# PWR_0V9_20A.net
KiCad netlist of a schematic drawn in Altium Designer
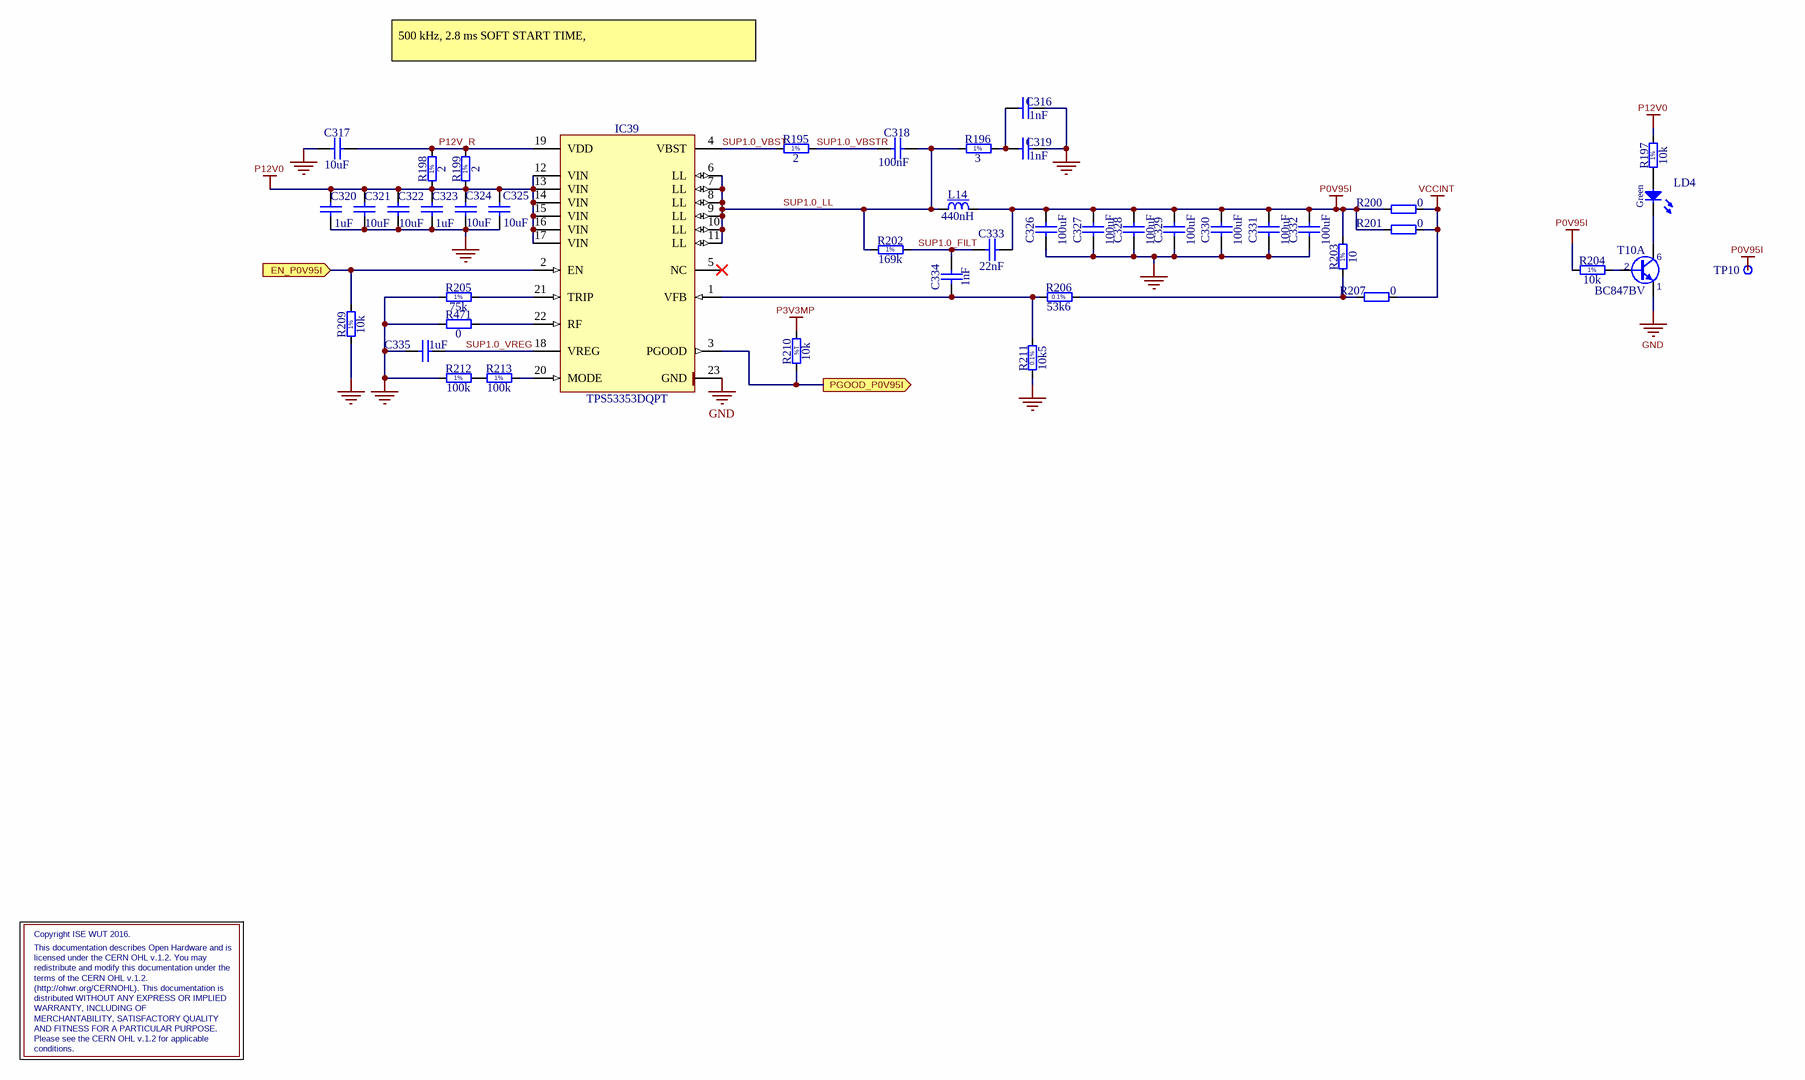
[diagram p0: PWR_0V9_20A.SchDoc]

(export (version "E")
  (design (tool "Eeschema 10.0.6"))
  (components
    (comp (ref "C316")
      (value "1nF")
      (footprint "CAPC1005X55N")
      (description "Non-polarised capacitor")
      (fields
        (field (name "MANUFACTURER PART NUMBER") "CC0402_1NF_50V_10%_X7R")
        (field (name "MANUFACTURER") "GENERIC")
        (field (name "AUTHOR") "CERN DEM JLC")
      )
      (libsource (lib "Capacitors") (part "Capacitor - non polarized"))
    )
    (comp (ref "C317")
      (value "10uF")
      (footprint "CAPC3216X180N")
      (description "Non-polarised capacitor")
      (fields
        (field (name "MANUFACTURER PART NUMBER") "CC1206_10uF_25V_10%_X7R")
        (field (name "MANUFACTURER") "GENERIC")
        (field (name "AUTHOR") "CERN DEM JLC")
      )
      (libsource (lib "Capacitors") (part "Capacitor - non polarized"))
    )
    (comp (ref "C318")
      (value "100nF")
      (footprint "CAPC1005X55N")
      (description "Non-polarised capacitor")
      (fields
        (field (name "MANUFACTURER PART NUMBER") "CC0402_100NF_16V_10%_X5R")
        (field (name "MANUFACTURER") "GENERIC")
        (field (name "AUTHOR") "CERN DEM JLC")
      )
      (libsource (lib "Capacitors") (part "Capacitor - non polarized"))
    )
    (comp (ref "C319")
      (value "1nF")
      (footprint "CAPC1005X55N")
      (description "Non-polarised capacitor")
      (fields
        (field (name "MANUFACTURER PART NUMBER") "CC0402_1NF_50V_10%_X7R")
        (field (name "MANUFACTURER") "GENERIC")
        (field (name "AUTHOR") "CERN DEM JLC")
      )
      (libsource (lib "Capacitors") (part "Capacitor - non polarized"))
    )
    (comp (ref "C320")
      (value "1uF")
      (footprint "CAPC1608X87N")
      (description "Non-polarised capacitor")
      (fields
        (field (name "MANUFACTURER PART NUMBER") "CC0603_1UF_25V_10%_X7R")
        (field (name "MANUFACTURER") "GENERIC")
        (field (name "AUTHOR") "CERN DEM JLC")
      )
      (libsource (lib "Capacitors") (part "Capacitor - non polarized"))
    )
    (comp (ref "C321")
      (value "10uF")
      (footprint "CAPC3216X180N")
      (description "Non-polarised capacitor")
      (fields
        (field (name "MANUFACTURER PART NUMBER") "CC1206_10uF_25V_10%_X7R")
        (field (name "MANUFACTURER") "GENERIC")
        (field (name "AUTHOR") "CERN DEM JLC")
      )
      (libsource (lib "Capacitors") (part "Capacitor - non polarized"))
    )
    (comp (ref "C322")
      (value "10uF")
      (footprint "CAPC3216X180N")
      (description "Non-polarised capacitor")
      (fields
        (field (name "MANUFACTURER PART NUMBER") "CC1206_10uF_25V_10%_X7R")
        (field (name "MANUFACTURER") "GENERIC")
        (field (name "AUTHOR") "CERN DEM JLC")
      )
      (libsource (lib "Capacitors") (part "Capacitor - non polarized"))
    )
    (comp (ref "C323")
      (value "1uF")
      (footprint "CAPC1608X87N")
      (description "Non-polarised capacitor")
      (fields
        (field (name "MANUFACTURER PART NUMBER") "CC0603_1UF_25V_10%_X7R")
        (field (name "MANUFACTURER") "GENERIC")
        (field (name "AUTHOR") "CERN DEM JLC")
      )
      (libsource (lib "Capacitors") (part "Capacitor - non polarized"))
    )
    (comp (ref "C324")
      (value "10uF")
      (footprint "CAPC3216X180N")
      (description "Non-polarised capacitor")
      (fields
        (field (name "MANUFACTURER PART NUMBER") "CC1206_10uF_25V_10%_X7R")
        (field (name "MANUFACTURER") "GENERIC")
        (field (name "AUTHOR") "CERN DEM JLC")
      )
      (libsource (lib "Capacitors") (part "Capacitor - non polarized"))
    )
    (comp (ref "C325")
      (value "10uF")
      (footprint "CAPC3216X180N")
      (description "Non-polarised capacitor")
      (fields
        (field (name "MANUFACTURER PART NUMBER") "CC1206_10uF_25V_10%_X7R")
        (field (name "MANUFACTURER") "GENERIC")
        (field (name "AUTHOR") "CERN DEM JLC")
      )
      (libsource (lib "Capacitors") (part "Capacitor - non polarized"))
    )
    (comp (ref "C326")
      (value "100uF")
      (footprint "CAPC3216X180N")
      (description "Non-polarised capacitor")
      (fields
        (field (name "MANUFACTURER PART NUMBER") "CC1206_100UF_6.3V_20%_X5R")
        (field (name "MANUFACTURER") "GENERIC")
        (field (name "AUTHOR") "CERN DEM JLC")
      )
      (libsource (lib "Capacitors") (part "Capacitor - non polarized"))
    )
    (comp (ref "C327")
      (value "100uF")
      (footprint "CAPC3216X180N")
      (description "Non-polarised capacitor")
      (fields
        (field (name "MANUFACTURER PART NUMBER") "CC1206_100UF_6.3V_20%_X5R")
        (field (name "MANUFACTURER") "GENERIC")
        (field (name "AUTHOR") "CERN DEM JLC")
      )
      (libsource (lib "Capacitors") (part "Capacitor - non polarized"))
    )
    (comp (ref "C328")
      (value "100uF")
      (footprint "CAPC3216X180N")
      (description "Non-polarised capacitor")
      (fields
        (field (name "MANUFACTURER PART NUMBER") "CC1206_100UF_6.3V_20%_X5R")
        (field (name "MANUFACTURER") "GENERIC")
        (field (name "AUTHOR") "CERN DEM JLC")
      )
      (libsource (lib "Capacitors") (part "Capacitor - non polarized"))
    )
    (comp (ref "C329")
      (value "100uF")
      (footprint "CAPC3216X180N")
      (description "Non-polarised capacitor")
      (fields
        (field (name "MANUFACTURER PART NUMBER") "CC1206_100UF_6.3V_20%_X5R")
        (field (name "MANUFACTURER") "GENERIC")
        (field (name "AUTHOR") "CERN DEM JLC")
      )
      (libsource (lib "Capacitors") (part "Capacitor - non polarized"))
    )
    (comp (ref "C330")
      (value "100uF")
      (footprint "CAPC3216X180N")
      (description "Non-polarised capacitor")
      (fields
        (field (name "MANUFACTURER PART NUMBER") "CC1206_100UF_6.3V_20%_X5R")
        (field (name "MANUFACTURER") "GENERIC")
        (field (name "AUTHOR") "CERN DEM JLC")
      )
      (libsource (lib "Capacitors") (part "Capacitor - non polarized"))
    )
    (comp (ref "C331")
      (value "100uF")
      (footprint "CAPC3216X180N")
      (description "Non-polarised capacitor")
      (fields
        (field (name "MANUFACTURER PART NUMBER") "CC1206_100UF_6.3V_20%_X5R")
        (field (name "MANUFACTURER") "GENERIC")
        (field (name "AUTHOR") "CERN DEM JLC")
      )
      (libsource (lib "Capacitors") (part "Capacitor - non polarized"))
    )
    (comp (ref "C332")
      (value "100uF")
      (footprint "CAPC3216X180N")
      (description "Non-polarised capacitor")
      (fields
        (field (name "MANUFACTURER PART NUMBER") "CC1206_100UF_6.3V_20%_X5R")
        (field (name "MANUFACTURER") "GENERIC")
        (field (name "AUTHOR") "CERN DEM JLC")
      )
      (libsource (lib "Capacitors") (part "Capacitor - non polarized"))
    )
    (comp (ref "C333")
      (value "22nF")
      (footprint "CAPC1608X87N")
      (description "Non-polarised capacitor")
      (fields
        (field (name "MANUFACTURER PART NUMBER") "CC0603_22NF_50V_10%_X7R")
        (field (name "MANUFACTURER") "GENERIC")
        (field (name "AUTHOR") "CERN DEM JLC")
      )
      (libsource (lib "Capacitors") (part "Capacitor - non polarized"))
    )
    (comp (ref "C334")
      (value "1nF")
      (footprint "CAPC1005X55N")
      (description "Non-polarised capacitor")
      (fields
        (field (name "MANUFACTURER PART NUMBER") "CC0402_1NF_50V_10%_X7R")
        (field (name "MANUFACTURER") "GENERIC")
        (field (name "AUTHOR") "CERN DEM JLC")
      )
      (libsource (lib "Capacitors") (part "Capacitor - non polarized"))
    )
    (comp (ref "C335")
      (value "1uF")
      (footprint "CAPC1608X87N")
      (description "Non-polarised capacitor")
      (fields
        (field (name "MANUFACTURER PART NUMBER") "CC0603_1UF_25V_10%_X7R")
        (field (name "MANUFACTURER") "GENERIC")
        (field (name "AUTHOR") "CERN DEM JLC")
      )
      (libsource (lib "Capacitors") (part "Capacitor - non polarized"))
    )
    (comp (ref "IC39")
      (value "TPS53353DQPT")
      (footprint "SON50P500X600X150-23N-R334X557")
      (description "1.5V to 15V Input (4.5V to 25V Bias), 20A Synchronous Buck SWIFT™ Converter with Eco-mode™")
      (fields (field (name "MANUFACTURER") "TEXAS INSTRUMENTS"))
      (libsource (lib "TP_LIB") (part "TPS53353DQPT"))
    )
    (comp (ref "L14")
      (value "440nH")
      (footprint "IND_PULSE_PA0513")
      (description "Inductor With Core")
      (fields
        (field (name "MANUFACTURER PART NUMBER") "PA0513.441NLT")
        (field (name "MANUFACTURER") "PULSE ELECTRONICS")
        (field (name "AUTHOR") "CERN DEM JLC")
      )
      (libsource (lib "Inductors & Transformers") (part "Inductor With Magnetic core"))
    )
    (comp (ref "LD4")
      (value "Green")
      (footprint "LED_OSRAM_LGL29K")
      (description "LED Green 1C 2A")
      (fields
        (field (name "MANUFACTURER PART NUMBER") "LG L29K-G2J1-24-Z")
        (field (name "MANUFACTURER") "OSRAM")
        (field (name "AUTHOR") "CERN DEM JLC")
      )
      (libsource (lib "ICs And Semiconductors") (part "LED Green 1C 2A"))
    )
    (comp (ref "R195")
      (value "2")
      (footprint "RESC1608X55N")
      (description "Resistor - 1%")
      (fields
        (field (name "MANUFACTURER PART NUMBER") "R0603_2R_1%_0.1W_200PPM")
        (field (name "MANUFACTURER") "GENERIC")
        (field (name "AUTHOR") "CERN DEM JLC")
      )
      (libsource (lib "Resistors") (part "Resistor - 1%"))
    )
    (comp (ref "R196")
      (value "3")
      (footprint "RESC3216X65N")
      (description "Resistor - 1%")
      (fields
        (field (name "MANUFACTURER PART NUMBER") "R1206_3R_1%_0.25W_200PPM")
        (field (name "MANUFACTURER") "GENERIC")
        (field (name "AUTHOR") "CERN DEM JLC")
      )
      (libsource (lib "Resistors") (part "Resistor - 1%"))
    )
    (comp (ref "R197")
      (value "10k")
      (footprint "RESC1005X40N")
      (description "Resistor - 1%")
      (fields
        (field (name "PART NUMBER") "R0402_10K_1%_0.0625W_100PPM")
        (field (name "POWER") "0.0625W")
        (field (name "AUTHOR") "CERN DEM JLC")
      )
      (libsource (lib "Resistors") (part "Resistor - 1%"))
    )
    (comp (ref "R198")
      (value "2")
      (footprint "RESC1608X55N")
      (description "Resistor - 1%")
      (fields
        (field (name "MANUFACTURER PART NUMBER") "R0603_2R_1%_0.1W_200PPM")
        (field (name "MANUFACTURER") "GENERIC")
        (field (name "AUTHOR") "CERN DEM JLC")
      )
      (libsource (lib "Resistors") (part "Resistor - 1%"))
    )
    (comp (ref "R199")
      (value "2")
      (footprint "RESC1608X55N")
      (description "Resistor - 1%")
      (fields
        (field (name "MANUFACTURER PART NUMBER") "R0603_2R_1%_0.1W_200PPM")
        (field (name "MANUFACTURER") "GENERIC")
        (field (name "AUTHOR") "CERN DEM JLC")
      )
      (libsource (lib "Resistors") (part "Resistor - 1%"))
    )
    (comp (ref "R200")
      (value "0")
      (footprint "RESC6331X70N")
      (description "Resistor")
      (fields
        (field (name "MANUFACTURER PART NUMBER") "R2512_0R_JUMPER")
        (field (name "MANUFACTURER") "GENERIC")
        (field (name "AUTHOR") "CERN DEM JLC")
      )
      (libsource (lib "Resistors") (part "Resistor"))
    )
    (comp (ref "R201")
      (value "0")
      (footprint "RESC6331X70N")
      (description "Resistor")
      (fields
        (field (name "MANUFACTURER PART NUMBER") "R2512_0R_JUMPER")
        (field (name "MANUFACTURER") "GENERIC")
        (field (name "AUTHOR") "CERN DEM JLC")
      )
      (libsource (lib "Resistors") (part "Resistor"))
    )
    (comp (ref "R202")
      (value "169k")
      (footprint "RESC1608X55N")
      (description "Resistor - 1%")
      (fields
        (field (name "MANUFACTURER PART NUMBER") "R0603_169K_1%_0.1W_100PPM")
        (field (name "MANUFACTURER") "GENERIC")
        (field (name "AUTHOR") "CERN DEM JLC")
      )
      (libsource (lib "Resistors") (part "Resistor - 1%"))
    )
    (comp (ref "R203")
      (value "10")
      (footprint "RESC1005X40N")
      (description "Resistor - 1%")
      (fields
        (field (name "MANUFACTURER PART NUMBER") "R0402_10R_1%_0.0625W_200PPM")
        (field (name "MANUFACTURER") "GENERIC")
        (field (name "AUTHOR") "CERN DEM JLC")
      )
      (libsource (lib "Resistors") (part "Resistor - 1%"))
    )
    (comp (ref "R204")
      (value "10k")
      (footprint "RESC1005X40N")
      (description "Resistor - 1%")
      (fields
        (field (name "MANUFACTURER PART NUMBER") "R0402_10K_1%_0.0625W_100PPM")
        (field (name "MANUFACTURER") "GENERIC")
        (field (name "AUTHOR") "CERN DEM JLC")
      )
      (libsource (lib "Resistors") (part "Resistor - 1%"))
    )
    (comp (ref "R205")
      (value "75k")
      (footprint "RESC1005X40N")
      (description "Resistor - 1%")
      (fields
        (field (name "MANUFACTURER PART NUMBER") "R0402_75K_1%_0.0625W_100PPM")
        (field (name "MANUFACTURER") "GENERIC")
        (field (name "AUTHOR") "CERN DEM JLC")
      )
      (libsource (lib "Resistors") (part "Resistor - 1%"))
    )
    (comp (ref "R206")
      (value "53k6")
      (footprint "RESC1608X55N")
      (description "Resistor - 0.1%")
      (fields
        (field (name "PART NUMBER") "R0603_53K6_0.1%_0.063W_10PPM")
        (field (name "POWER") "0.063W")
        (field (name "AUTHOR") "CERN DEM JLC")
      )
      (libsource (lib "Resistors") (part "Resistor - 0.1%"))
    )
    (comp (ref "R207")
      (value "0")
      (footprint "RESC6331X70N")
      (description "Resistor")
      (fields
        (field (name "MANUFACTURER PART NUMBER") "R2512_0R_JUMPER")
        (field (name "MANUFACTURER") "GENERIC")
        (field (name "AUTHOR") "CERN DEM JLC")
      )
      (libsource (lib "Resistors") (part "Resistor"))
    )
    (comp (ref "R209")
      (value "10k")
      (footprint "RESC1005X40N")
      (description "Resistor - 1%")
      (fields
        (field (name "MANUFACTURER PART NUMBER") "R0402_10K_1%_0.0625W_100PPM")
        (field (name "MANUFACTURER") "GENERIC")
        (field (name "AUTHOR") "CERN DEM JLC")
      )
      (libsource (lib "Resistors") (part "Resistor - 1%"))
    )
    (comp (ref "R210")
      (value "10k")
      (footprint "RESC1005X40N")
      (description "Resistor - 1%")
      (fields
        (field (name "MANUFACTURER PART NUMBER") "R0402_10K_1%_0.0625W_100PPM")
        (field (name "MANUFACTURER") "GENERIC")
        (field (name "AUTHOR") "CERN DEM JLC")
      )
      (libsource (lib "Resistors") (part "Resistor - 1%"))
    )
    (comp (ref "R211")
      (value "10k5")
      (footprint "RESC1608X55N")
      (description "Resistor - 0.1%")
      (fields
        (field (name "PART NUMBER") "R0603_10K5_0.1%_0.063W_10PPM")
        (field (name "POWER") "0.063W")
        (field (name "AUTHOR") "CERN DEM JLC")
      )
      (libsource (lib "Resistors") (part "Resistor - 0.1%"))
    )
    (comp (ref "R212")
      (value "100k")
      (footprint "RESC1005X40N")
      (description "Resistor - 1%")
      (fields
        (field (name "MANUFACTURER PART NUMBER") "R0402_100K_1%_0.0625W_100PPM")
        (field (name "MANUFACTURER") "GENERIC")
        (field (name "AUTHOR") "CERN DEM JLC")
      )
      (libsource (lib "Resistors") (part "Resistor - 1%"))
    )
    (comp (ref "R213")
      (value "100k")
      (footprint "RESC1005X40N")
      (description "Resistor - 1%")
      (fields
        (field (name "MANUFACTURER PART NUMBER") "R0402_100K_1%_0.0625W_100PPM")
        (field (name "MANUFACTURER") "GENERIC")
        (field (name "AUTHOR") "CERN DEM JLC")
      )
      (libsource (lib "Resistors") (part "Resistor - 1%"))
    )
    (comp (ref "R471")
      (value "0")
      (footprint "RESC1005X40N")
      (description "Resistor")
      (fields
        (field (name "PART NUMBER") "R0402_0R_JUMPER")
        (field (name "MANUFACTURER") "GENERIC")
        (field (name "AUTHOR") "CERN DEM JLC")
      )
      (libsource (lib "Resistors") (part "Resistor"))
    )
    (comp (ref "T10")
      (value "BC847BV")
      (footprint "SOTFL50P160X60-6N")
      (description "45V, 100mA NPN General Purpose Double Transistor")
      (fields (field (name "MANUFACTURER") "NXP SEMICONDUCTORS") (field (name "AUTHOR") "CERN DEM JLC"))
      (libsource (lib "ICs And Semiconductors") (part "BC847BV"))
    )
    (comp (ref "TP10")
      (value "Test Point")
      (footprint "TPS127")
      (fields (field (name "PART NUMBER") "SMD_PAD_1.27X1.27MM") (field (name "AUTHOR") "CERN DEM JLC"))
      (libsource (lib "Eletro-mechanical") (part "Test Point"))
    )
  )
  (nets
    (net (code "1") (name "/EN_P0V95I") (class "Default")
      (node (ref "IC39") (pin "2") (pinfunction "EN_2") (pintype "input"))
      (node (ref "R209") (pin "1") (pinfunction "1_1") (pintype "passive"))
    )
    (net (code "2") (name "/P12V_R") (class "Default")
      (node (ref "C317") (pin "1") (pinfunction "1_1") (pintype "passive"))
      (node (ref "IC39") (pin "19") (pinfunction "VDD_19") (pintype "power_in"))
      (node (ref "R198") (pin "2") (pinfunction "2_2") (pintype "passive"))
      (node (ref "R199") (pin "2") (pinfunction "2_2") (pintype "passive"))
    )
    (net (code "3") (name "/PGOOD_P0V95I") (class "Default")
      (node (ref "IC39") (pin "3") (pinfunction "PGOOD_3") (pintype "output"))
      (node (ref "R210") (pin "1") (pinfunction "1_1") (pintype "passive"))
    )
    (net (code "4") (name "/SUP1.0_FILT") (class "Default")
      (node (ref "C333") (pin "1") (pinfunction "1_1") (pintype "passive"))
      (node (ref "C334") (pin "2") (pinfunction "2_2") (pintype "passive"))
      (node (ref "R202") (pin "2") (pinfunction "2_2") (pintype "passive"))
    )
    (net (code "5") (name "/SUP1.0_LL") (class "Default")
      (node (ref "C318") (pin "2") (pinfunction "2_2") (pintype "passive"))
      (node (ref "IC39") (pin "10") (pinfunction "LL_10") (pintype "bidirectional"))
      (node (ref "IC39") (pin "11") (pinfunction "LL_11") (pintype "bidirectional"))
      (node (ref "IC39") (pin "6") (pinfunction "LL_6") (pintype "bidirectional"))
      (node (ref "IC39") (pin "7") (pinfunction "LL_7") (pintype "bidirectional"))
      (node (ref "IC39") (pin "8") (pinfunction "LL_8") (pintype "bidirectional"))
      (node (ref "IC39") (pin "9") (pinfunction "LL_9") (pintype "bidirectional"))
      (node (ref "L14") (pin "1") (pinfunction "1_1") (pintype "passive"))
      (node (ref "R196") (pin "1") (pinfunction "1_1") (pintype "passive"))
      (node (ref "R202") (pin "1") (pinfunction "1_1") (pintype "passive"))
    )
    (net (code "6") (name "/SUP1.0_VBST") (class "Default")
      (node (ref "IC39") (pin "4") (pinfunction "VBST_4") (pintype "power_in"))
      (node (ref "R195") (pin "1") (pinfunction "1_1") (pintype "passive"))
    )
    (net (code "7") (name "/SUP1.0_VBSTR") (class "Default")
      (node (ref "C318") (pin "1") (pinfunction "1_1") (pintype "passive"))
      (node (ref "R195") (pin "2") (pinfunction "2_2") (pintype "passive"))
    )
    (net (code "8") (name "/SUP1.0_VREG") (class "Default")
      (node (ref "C335") (pin "1") (pinfunction "1_1") (pintype "passive"))
      (node (ref "IC39") (pin "18") (pinfunction "VREG_18") (pintype "power_in"))
    )
    (net (code "9") (name "GND") (class "Default")
      (node (ref "C316") (pin "2") (pinfunction "2_2") (pintype "passive"))
      (node (ref "C317") (pin "2") (pinfunction "2_2") (pintype "passive"))
      (node (ref "C319") (pin "2") (pinfunction "2_2") (pintype "passive"))
      (node (ref "C320") (pin "1") (pinfunction "1_1") (pintype "passive"))
      (node (ref "C321") (pin "1") (pinfunction "1_1") (pintype "passive"))
      (node (ref "C322") (pin "1") (pinfunction "1_1") (pintype "passive"))
      (node (ref "C323") (pin "1") (pinfunction "1_1") (pintype "passive"))
      (node (ref "C324") (pin "1") (pinfunction "1_1") (pintype "passive"))
      (node (ref "C325") (pin "1") (pinfunction "1_1") (pintype "passive"))
      (node (ref "C326") (pin "1") (pinfunction "1_1") (pintype "passive"))
      (node (ref "C327") (pin "1") (pinfunction "1_1") (pintype "passive"))
      (node (ref "C328") (pin "1") (pinfunction "1_1") (pintype "passive"))
      (node (ref "C329") (pin "1") (pinfunction "1_1") (pintype "passive"))
      (node (ref "C330") (pin "1") (pinfunction "1_1") (pintype "passive"))
      (node (ref "C331") (pin "1") (pinfunction "1_1") (pintype "passive"))
      (node (ref "C332") (pin "1") (pinfunction "1_1") (pintype "passive"))
      (node (ref "C335") (pin "2") (pinfunction "2_2") (pintype "passive"))
      (node (ref "IC39") (pin "23") (pinfunction "GND_23") (pintype "power_in"))
      (node (ref "R205") (pin "1") (pinfunction "1_1") (pintype "passive"))
      (node (ref "R209") (pin "2") (pinfunction "2_2") (pintype "passive"))
      (node (ref "R211") (pin "1") (pinfunction "1_1") (pintype "passive"))
      (node (ref "R212") (pin "1") (pinfunction "1_1") (pintype "passive"))
      (node (ref "R471") (pin "1") (pinfunction "1_1") (pintype "passive"))
      (node (ref "T10") (pin "1") (pinfunction "E_1") (pintype "passive"))
    )
    (net (code "10") (name "Net-(C316-Pad1)") (class "Default")
      (node (ref "C316") (pin "1") (pinfunction "1_1") (pintype "passive"))
      (node (ref "C319") (pin "1") (pinfunction "1_1") (pintype "passive"))
      (node (ref "R196") (pin "2") (pinfunction "2_2") (pintype "passive"))
    )
    (net (code "11") (name "Net-(IC39-MODE)") (class "Default")
      (node (ref "IC39") (pin "20") (pinfunction "MODE_20") (pintype "input"))
      (node (ref "R213") (pin "2") (pinfunction "2_2") (pintype "passive"))
    )
    (net (code "12") (name "Net-(IC39-RF)") (class "Default")
      (node (ref "IC39") (pin "22") (pinfunction "RF_22") (pintype "input"))
      (node (ref "R471") (pin "2") (pinfunction "2_2") (pintype "passive"))
    )
    (net (code "13") (name "Net-(IC39-TRIP)") (class "Default")
      (node (ref "IC39") (pin "21") (pinfunction "TRIP_21") (pintype "input"))
      (node (ref "R205") (pin "2") (pinfunction "2_2") (pintype "passive"))
    )
    (net (code "14") (name "Net-(IC39-VFB)") (class "Default")
      (node (ref "C334") (pin "1") (pinfunction "1_1") (pintype "passive"))
      (node (ref "IC39") (pin "1") (pinfunction "VFB_1") (pintype "input"))
      (node (ref "R206") (pin "1") (pinfunction "1_1") (pintype "passive"))
      (node (ref "R211") (pin "2") (pinfunction "2_2") (pintype "passive"))
    )
    (net (code "15") (name "Net-(LD4-A)") (class "Default")
      (node (ref "LD4") (pin "2") (pinfunction "A_2") (pintype "passive"))
      (node (ref "R197") (pin "1") (pinfunction "1_1") (pintype "passive"))
    )
    (net (code "16") (name "Net-(LD4-C)") (class "Default")
      (node (ref "LD4") (pin "1") (pinfunction "C_1") (pintype "passive"))
      (node (ref "T10") (pin "6") (pinfunction "C_6") (pintype "passive"))
    )
    (net (code "17") (name "Net-(R203-Pad1)") (class "Default")
      (node (ref "R203") (pin "1") (pinfunction "1_1") (pintype "passive"))
      (node (ref "R206") (pin "2") (pinfunction "2_2") (pintype "passive"))
      (node (ref "R207") (pin "1") (pinfunction "1_1") (pintype "passive"))
    )
    (net (code "18") (name "Net-(R212-Pad2)") (class "Default")
      (node (ref "R212") (pin "2") (pinfunction "2_2") (pintype "passive"))
      (node (ref "R213") (pin "1") (pinfunction "1_1") (pintype "passive"))
    )
    (net (code "19") (name "Net-(T10A-B)") (class "Default")
      (node (ref "R204") (pin "2") (pinfunction "2_2") (pintype "passive"))
      (node (ref "T10") (pin "2") (pinfunction "B_2") (pintype "passive"))
    )
    (net (code "20") (name "P0V95I") (class "Default")
      (node (ref "C326") (pin "2") (pinfunction "2_2") (pintype "passive"))
      (node (ref "C327") (pin "2") (pinfunction "2_2") (pintype "passive"))
      (node (ref "C328") (pin "2") (pinfunction "2_2") (pintype "passive"))
      (node (ref "C329") (pin "2") (pinfunction "2_2") (pintype "passive"))
      (node (ref "C330") (pin "2") (pinfunction "2_2") (pintype "passive"))
      (node (ref "C331") (pin "2") (pinfunction "2_2") (pintype "passive"))
      (node (ref "C332") (pin "2") (pinfunction "2_2") (pintype "passive"))
      (node (ref "C333") (pin "2") (pinfunction "2_2") (pintype "passive"))
      (node (ref "L14") (pin "2") (pinfunction "2_2") (pintype "passive"))
      (node (ref "R200") (pin "1") (pinfunction "1_1") (pintype "passive"))
      (node (ref "R201") (pin "1") (pinfunction "1_1") (pintype "passive"))
      (node (ref "R203") (pin "2") (pinfunction "2_2") (pintype "passive"))
      (node (ref "R204") (pin "1") (pinfunction "1_1") (pintype "passive"))
      (node (ref "TP10") (pin "1") (pinfunction "1_1") (pintype "bidirectional"))
    )
    (net (code "21") (name "P3V3MP") (class "Default")
      (node (ref "R210") (pin "2") (pinfunction "2_2") (pintype "passive"))
    )
    (net (code "22") (name "P12V0") (class "Default")
      (node (ref "C320") (pin "2") (pinfunction "2_2") (pintype "passive"))
      (node (ref "C321") (pin "2") (pinfunction "2_2") (pintype "passive"))
      (node (ref "C322") (pin "2") (pinfunction "2_2") (pintype "passive"))
      (node (ref "C323") (pin "2") (pinfunction "2_2") (pintype "passive"))
      (node (ref "C324") (pin "2") (pinfunction "2_2") (pintype "passive"))
      (node (ref "C325") (pin "2") (pinfunction "2_2") (pintype "passive"))
      (node (ref "IC39") (pin "12") (pinfunction "VIN_12") (pintype "power_in"))
      (node (ref "IC39") (pin "13") (pinfunction "VIN_13") (pintype "power_in"))
      (node (ref "IC39") (pin "14") (pinfunction "VIN_14") (pintype "power_in"))
      (node (ref "IC39") (pin "15") (pinfunction "VIN_15") (pintype "power_in"))
      (node (ref "IC39") (pin "16") (pinfunction "VIN_16") (pintype "power_in"))
      (node (ref "IC39") (pin "17") (pinfunction "VIN_17") (pintype "power_in"))
      (node (ref "R197") (pin "2") (pinfunction "2_2") (pintype "passive"))
      (node (ref "R198") (pin "1") (pinfunction "1_1") (pintype "passive"))
      (node (ref "R199") (pin "1") (pinfunction "1_1") (pintype "passive"))
    )
    (net (code "23") (name "VCCINT") (class "Default")
      (node (ref "R200") (pin "2") (pinfunction "2_2") (pintype "passive"))
      (node (ref "R201") (pin "2") (pinfunction "2_2") (pintype "passive"))
      (node (ref "R207") (pin "2") (pinfunction "2_2") (pintype "passive"))
    )
    (net (code "24") (name "unconnected-(IC39-NC-Pad5)") (class "Default")
      (node (ref "IC39") (pin "5") (pinfunction "NC_5") (pintype "passive+no_connect"))
    )
  )
)
